# cryobondr-sense1-vlaqc-test2.net
KiCad netlist of a schematic drawn in EAGLE
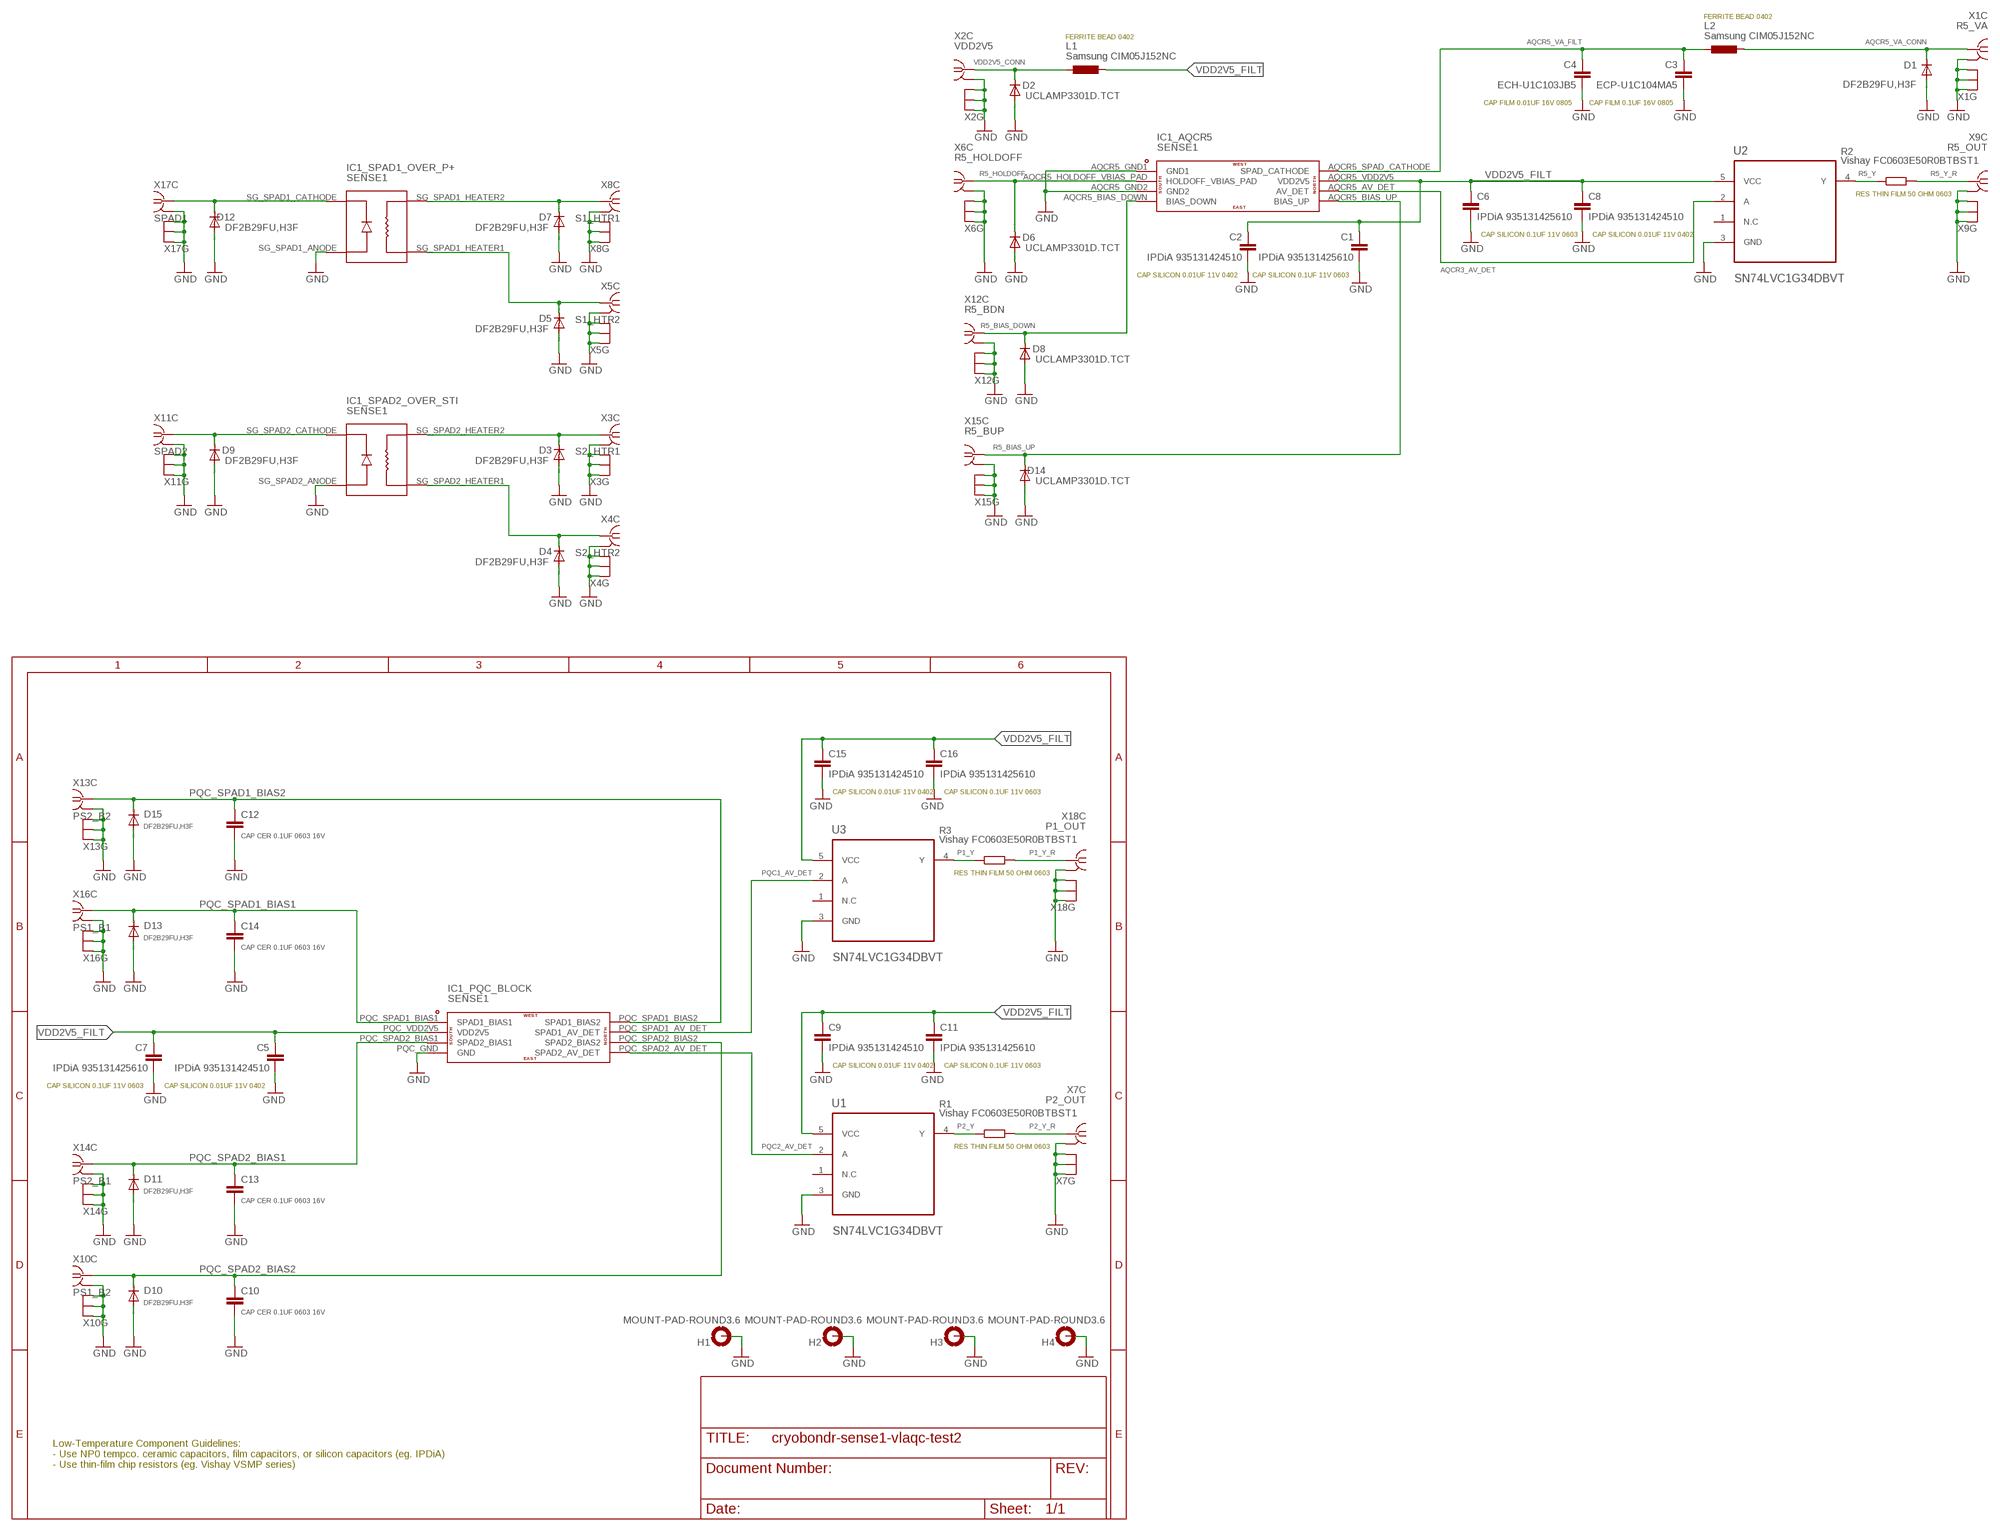
[diagram p0: schematic, sheet 1]

(export (version "E")
  (design (tool "Eeschema 10.0.6"))
  (components
    (comp (ref "C1")
      (value "IPDiA 935131425610")
      (footprint "eagle-import:C0603")
      (libsource (lib "eagle-import") (part "C-EUC0603"))
    )
    (comp (ref "C2")
      (value "IPDiA 935131424510")
      (footprint "eagle-import:C0402")
      (libsource (lib "eagle-import") (part "C-EUC0402"))
    )
    (comp (ref "C3")
      (value "ECP-U1C104MA5")
      (footprint "eagle-import:C0805")
      (libsource (lib "eagle-import") (part "C-EUC0805"))
    )
    (comp (ref "C4")
      (value "ECH-U1C103JB5")
      (footprint "eagle-import:C0805")
      (libsource (lib "eagle-import") (part "C-EUC0805"))
    )
    (comp (ref "C5")
      (value "IPDiA 935131424510")
      (footprint "eagle-import:C0402")
      (libsource (lib "eagle-import") (part "C-EUC0402"))
    )
    (comp (ref "C6")
      (value "IPDiA 935131425610")
      (footprint "eagle-import:C0603")
      (libsource (lib "eagle-import") (part "C-EUC0603"))
    )
    (comp (ref "C7")
      (value "IPDiA 935131425610")
      (footprint "eagle-import:C0603")
      (libsource (lib "eagle-import") (part "C-EUC0603"))
    )
    (comp (ref "C8")
      (value "IPDiA 935131424510")
      (footprint "eagle-import:C0402")
      (libsource (lib "eagle-import") (part "C-EUC0402"))
    )
    (comp (ref "C9")
      (value "IPDiA 935131424510")
      (footprint "eagle-import:C0402")
      (libsource (lib "eagle-import") (part "C-EUC0402"))
    )
    (comp (ref "C10")
      (value "CAP CER 0.1UF 0603 16V")
      (footprint "eagle-import:C0603")
      (libsource (lib "eagle-import") (part "C-EUC0603"))
    )
    (comp (ref "C11")
      (value "IPDiA 935131425610")
      (footprint "eagle-import:C0603")
      (libsource (lib "eagle-import") (part "C-EUC0603"))
    )
    (comp (ref "C12")
      (value "CAP CER 0.1UF 0603 16V")
      (footprint "eagle-import:C0603")
      (libsource (lib "eagle-import") (part "C-EUC0603"))
    )
    (comp (ref "C13")
      (value "CAP CER 0.1UF 0603 16V")
      (footprint "eagle-import:C0603")
      (libsource (lib "eagle-import") (part "C-EUC0603"))
    )
    (comp (ref "C14")
      (value "CAP CER 0.1UF 0603 16V")
      (footprint "eagle-import:C0603")
      (libsource (lib "eagle-import") (part "C-EUC0603"))
    )
    (comp (ref "C15")
      (value "IPDiA 935131424510")
      (footprint "eagle-import:C0402")
      (libsource (lib "eagle-import") (part "C-EUC0402"))
    )
    (comp (ref "C16")
      (value "IPDiA 935131425610")
      (footprint "eagle-import:C0603")
      (libsource (lib "eagle-import") (part "C-EUC0603"))
    )
    (comp (ref "D1")
      (value "DF2B29FU,H3F")
      (footprint "eagle-import:SOD323-R")
      (libsource (lib "eagle-import") (part "DIODE-SOD323-R"))
    )
    (comp (ref "D2")
      (value "UCLAMP3301D.TCT")
      (footprint "eagle-import:SOD323-R")
      (libsource (lib "eagle-import") (part "DIODE-SOD323-R"))
    )
    (comp (ref "D3")
      (value "DF2B29FU,H3F")
      (footprint "eagle-import:SOD323-R")
      (libsource (lib "eagle-import") (part "DIODE-SOD323-R"))
    )
    (comp (ref "D4")
      (value "DF2B29FU,H3F")
      (footprint "eagle-import:SOD323-R")
      (libsource (lib "eagle-import") (part "DIODE-SOD323-R"))
    )
    (comp (ref "D5")
      (value "DF2B29FU,H3F")
      (footprint "eagle-import:SOD323-R")
      (libsource (lib "eagle-import") (part "DIODE-SOD323-R"))
    )
    (comp (ref "D6")
      (value "UCLAMP3301D.TCT")
      (footprint "eagle-import:SOD323-R")
      (libsource (lib "eagle-import") (part "DIODE-SOD323-R"))
    )
    (comp (ref "D7")
      (value "DF2B29FU,H3F")
      (footprint "eagle-import:SOD323-R")
      (libsource (lib "eagle-import") (part "DIODE-SOD323-R"))
    )
    (comp (ref "D8")
      (value "UCLAMP3301D.TCT")
      (footprint "eagle-import:SOD323-R")
      (libsource (lib "eagle-import") (part "DIODE-SOD323-R"))
    )
    (comp (ref "D9")
      (value "DF2B29FU,H3F")
      (footprint "eagle-import:SOD323-R")
      (libsource (lib "eagle-import") (part "DIODE-SOD323-R"))
    )
    (comp (ref "D10")
      (value "DF2B29FU,H3F")
      (footprint "eagle-import:SOD323-R")
      (libsource (lib "eagle-import") (part "DIODE-SOD323-R"))
    )
    (comp (ref "D11")
      (value "DF2B29FU,H3F")
      (footprint "eagle-import:SOD323-R")
      (libsource (lib "eagle-import") (part "DIODE-SOD323-R"))
    )
    (comp (ref "D12")
      (value "DF2B29FU,H3F")
      (footprint "eagle-import:SOD323-R")
      (libsource (lib "eagle-import") (part "DIODE-SOD323-R"))
    )
    (comp (ref "D13")
      (value "DF2B29FU,H3F")
      (footprint "eagle-import:SOD323-R")
      (libsource (lib "eagle-import") (part "DIODE-SOD323-R"))
    )
    (comp (ref "D14")
      (value "UCLAMP3301D.TCT")
      (footprint "eagle-import:SOD323-R")
      (libsource (lib "eagle-import") (part "DIODE-SOD323-R"))
    )
    (comp (ref "D15")
      (value "DF2B29FU,H3F")
      (footprint "eagle-import:SOD323-R")
      (libsource (lib "eagle-import") (part "DIODE-SOD323-R"))
    )
    (comp (ref "H1")
      (value "MOUNT-PAD-ROUND3.6")
      (footprint "eagle-import:3,6-PAD")
      (libsource (lib "eagle-import") (part "MOUNT-PAD-ROUND3.6"))
    )
    (comp (ref "H2")
      (value "MOUNT-PAD-ROUND3.6")
      (footprint "eagle-import:3,6-PAD")
      (libsource (lib "eagle-import") (part "MOUNT-PAD-ROUND3.6"))
    )
    (comp (ref "H3")
      (value "MOUNT-PAD-ROUND3.6")
      (footprint "eagle-import:3,6-PAD")
      (libsource (lib "eagle-import") (part "MOUNT-PAD-ROUND3.6"))
    )
    (comp (ref "H4")
      (value "MOUNT-PAD-ROUND3.6")
      (footprint "eagle-import:3,6-PAD")
      (libsource (lib "eagle-import") (part "MOUNT-PAD-ROUND3.6"))
    )
    (comp (ref "IC1")
      (value "SENSE1")
      (footprint "eagle-import:SENSE1-WIREBOND-VLAQC-TEST2")
      (libsource (lib "eagle-import") (part "SENSE1-WIREBOND-VLAQC-TEST2"))
    )
    (comp (ref "L1")
      (value "Samsung CIM05J152NC")
      (footprint "eagle-import:R0402")
      (libsource (lib "eagle-import") (part "INDUCTOR0402"))
    )
    (comp (ref "L2")
      (value "Samsung CIM05J152NC")
      (footprint "eagle-import:R0402")
      (libsource (lib "eagle-import") (part "INDUCTOR0402"))
    )
    (comp (ref "R1")
      (value "Vishay FC0603E50R0BTBST1")
      (footprint "eagle-import:R0603")
      (libsource (lib "eagle-import") (part "R-EU_R0603"))
    )
    (comp (ref "R2")
      (value "Vishay FC0603E50R0BTBST1")
      (footprint "eagle-import:R0603")
      (libsource (lib "eagle-import") (part "R-EU_R0603"))
    )
    (comp (ref "R3")
      (value "Vishay FC0603E50R0BTBST1")
      (footprint "eagle-import:R0603")
      (libsource (lib "eagle-import") (part "R-EU_R0603"))
    )
    (comp (ref "U1")
      (value "SN74LVC1G34DBVT")
      (footprint "eagle-import:SOT95P280X145-5N")
      (fields (field (name "SPICEPREFIX") "X"))
      (libsource (lib "eagle-import") (part "SN74LVC1G34DBVT"))
    )
    (comp (ref "U2")
      (value "SN74LVC1G34DBVT")
      (footprint "eagle-import:SOT95P280X145-5N")
      (fields (field (name "SPICEPREFIX") "X"))
      (libsource (lib "eagle-import") (part "SN74LVC1G34DBVT"))
    )
    (comp (ref "U3")
      (value "SN74LVC1G34DBVT")
      (footprint "eagle-import:SOT95P280X145-5N")
      (fields (field (name "SPICEPREFIX") "X"))
      (libsource (lib "eagle-import") (part "SN74LVC1G34DBVT"))
    )
    (comp (ref "X1")
      (value "R5_VA")
      (footprint "eagle-import:MMCX-SMT-BIGPADS")
      (libsource (lib "eagle-import") (part "MMCXBIGPAD"))
    )
    (comp (ref "X2")
      (value "VDD2V5")
      (footprint "eagle-import:MMCX-SMT-BIGPADS")
      (libsource (lib "eagle-import") (part "MMCXBIGPAD"))
    )
    (comp (ref "X3")
      (value "S2_HTR1")
      (footprint "eagle-import:MMCX-SMT-BIGPADS")
      (libsource (lib "eagle-import") (part "MMCXBIGPAD"))
    )
    (comp (ref "X4")
      (value "S2_HTR2")
      (footprint "eagle-import:MMCX-SMT-BIGPADS")
      (libsource (lib "eagle-import") (part "MMCXBIGPAD"))
    )
    (comp (ref "X5")
      (value "S1_HTR2")
      (footprint "eagle-import:MMCX-SMT-BIGPADS")
      (libsource (lib "eagle-import") (part "MMCXBIGPAD"))
    )
    (comp (ref "X6")
      (value "R5_HOLDOFF")
      (footprint "eagle-import:MMCX-SMT-BIGPADS")
      (libsource (lib "eagle-import") (part "MMCXBIGPAD"))
    )
    (comp (ref "X7")
      (value "P2_OUT")
      (footprint "eagle-import:MMCX-SMT-BIGPADS")
      (libsource (lib "eagle-import") (part "MMCXBIGPAD"))
    )
    (comp (ref "X8")
      (value "S1_HTR1")
      (footprint "eagle-import:MMCX-SMT-BIGPADS")
      (libsource (lib "eagle-import") (part "MMCXBIGPAD"))
    )
    (comp (ref "X9")
      (value "R5_OUT")
      (footprint "eagle-import:MMCX-SMT-BIGPADS")
      (libsource (lib "eagle-import") (part "MMCXBIGPAD"))
    )
    (comp (ref "X10")
      (value "PS1_B2")
      (footprint "eagle-import:MMCX-SMT-BIGPADS")
      (libsource (lib "eagle-import") (part "MMCXBIGPAD"))
    )
    (comp (ref "X11")
      (value "SPAD2")
      (footprint "eagle-import:MMCX-SMT-BIGPADS")
      (libsource (lib "eagle-import") (part "MMCXBIGPAD"))
    )
    (comp (ref "X12")
      (value "R5_BDN")
      (footprint "eagle-import:MMCX-SMT-BIGPADS")
      (libsource (lib "eagle-import") (part "MMCXBIGPAD"))
    )
    (comp (ref "X13")
      (value "PS2_B2")
      (footprint "eagle-import:MMCX-SMT-BIGPADS")
      (libsource (lib "eagle-import") (part "MMCXBIGPAD"))
    )
    (comp (ref "X14")
      (value "PS2_B1")
      (footprint "eagle-import:MMCX-SMT-BIGPADS")
      (libsource (lib "eagle-import") (part "MMCXBIGPAD"))
    )
    (comp (ref "X15")
      (value "R5_BUP")
      (footprint "eagle-import:MMCX-SMT-BIGPADS")
      (libsource (lib "eagle-import") (part "MMCXBIGPAD"))
    )
    (comp (ref "X16")
      (value "PS1_B1")
      (footprint "eagle-import:MMCX-SMT-BIGPADS")
      (libsource (lib "eagle-import") (part "MMCXBIGPAD"))
    )
    (comp (ref "X17")
      (value "SPAD1")
      (footprint "eagle-import:MMCX-SMT-BIGPADS")
      (libsource (lib "eagle-import") (part "MMCXBIGPAD"))
    )
    (comp (ref "X18")
      (value "P1_OUT")
      (footprint "eagle-import:MMCX-SMT-BIGPADS")
      (libsource (lib "eagle-import") (part "MMCXBIGPAD"))
    )
  )
  (nets
    (net (code "1") (name "/AQCR3_AV_DET") (class "Default")
      (node (ref "IC1") (pin "AQCR5_AV_DET") (pinfunction "AV_DET_AQCR5_AV_DET") (pintype "bidirectional"))
      (node (ref "U2") (pin "2") (pinfunction "A_2") (pintype "input"))
    )
    (net (code "2") (name "/AQCR5_VA_CONN") (class "Default")
      (node (ref "D1") (pin "C") (pinfunction "C_C") (pintype "passive"))
      (node (ref "L2") (pin "2") (pinfunction "P$2_2") (pintype "bidirectional"))
      (node (ref "X1") (pin "S") (pinfunction "1_S") (pintype "passive"))
    )
    (net (code "3") (name "/AQCR5_VA_FILT") (class "Default")
      (node (ref "C3") (pin "1") (pinfunction "1_1") (pintype "passive"))
      (node (ref "C4") (pin "1") (pinfunction "1_1") (pintype "passive"))
      (node (ref "IC1") (pin "AQCR5_SPAD_CATHODE") (pinfunction "SPAD_CATHODE_AQCR5_SPAD_CATHODE") (pintype "bidirectional"))
      (node (ref "L2") (pin "1") (pinfunction "P$1_1") (pintype "bidirectional"))
    )
    (net (code "4") (name "/P1_Y") (class "Default")
      (node (ref "R3") (pin "1") (pinfunction "1_1") (pintype "passive"))
      (node (ref "U3") (pin "4") (pinfunction "Y_4") (pintype "output"))
    )
    (net (code "5") (name "/P1_Y_R") (class "Default")
      (node (ref "R3") (pin "2") (pinfunction "2_2") (pintype "passive"))
      (node (ref "X18") (pin "S") (pinfunction "1_S") (pintype "passive"))
    )
    (net (code "6") (name "/P2_Y") (class "Default")
      (node (ref "R1") (pin "1") (pinfunction "1_1") (pintype "passive"))
      (node (ref "U1") (pin "4") (pinfunction "Y_4") (pintype "output"))
    )
    (net (code "7") (name "/P2_Y_R") (class "Default")
      (node (ref "R1") (pin "2") (pinfunction "2_2") (pintype "passive"))
      (node (ref "X7") (pin "S") (pinfunction "1_S") (pintype "passive"))
    )
    (net (code "8") (name "/PQC1_AV_DET") (class "Default")
      (node (ref "IC1") (pin "PQC_SPAD1_AV_DET") (pinfunction "SPAD1_AV_DET_PQC_SPAD1_AV_DET") (pintype "bidirectional"))
      (node (ref "U3") (pin "2") (pinfunction "A_2") (pintype "input"))
    )
    (net (code "9") (name "/PQC2_AV_DET") (class "Default")
      (node (ref "IC1") (pin "PQC_SPAD2_AV_DET") (pinfunction "SPAD2_AV_DET_PQC_SPAD2_AV_DET") (pintype "bidirectional"))
      (node (ref "U1") (pin "2") (pinfunction "A_2") (pintype "input"))
    )
    (net (code "10") (name "/PQC_SPAD1_BIAS1") (class "Default")
      (node (ref "C14") (pin "1") (pinfunction "1_1") (pintype "passive"))
      (node (ref "D13") (pin "C") (pinfunction "C_C") (pintype "passive"))
      (node (ref "IC1") (pin "PQC_SPAD1_BIAS1") (pinfunction "SPAD1_BIAS1_PQC_SPAD1_BIAS1") (pintype "bidirectional"))
      (node (ref "X16") (pin "S") (pinfunction "1_S") (pintype "passive"))
    )
    (net (code "11") (name "/PQC_SPAD1_BIAS2") (class "Default")
      (node (ref "C12") (pin "1") (pinfunction "1_1") (pintype "passive"))
      (node (ref "D15") (pin "C") (pinfunction "C_C") (pintype "passive"))
      (node (ref "IC1") (pin "PQC_SPAD1_BIAS2") (pinfunction "SPAD1_BIAS2_PQC_SPAD1_BIAS2") (pintype "bidirectional"))
      (node (ref "X13") (pin "S") (pinfunction "1_S") (pintype "passive"))
    )
    (net (code "12") (name "/PQC_SPAD2_BIAS1") (class "Default")
      (node (ref "C13") (pin "1") (pinfunction "1_1") (pintype "passive"))
      (node (ref "D11") (pin "C") (pinfunction "C_C") (pintype "passive"))
      (node (ref "IC1") (pin "PQC_SPAD2_BIAS1") (pinfunction "SPAD2_BIAS1_PQC_SPAD2_BIAS1") (pintype "bidirectional"))
      (node (ref "X14") (pin "S") (pinfunction "1_S") (pintype "passive"))
    )
    (net (code "13") (name "/PQC_SPAD2_BIAS2") (class "Default")
      (node (ref "C10") (pin "1") (pinfunction "1_1") (pintype "passive"))
      (node (ref "D10") (pin "C") (pinfunction "C_C") (pintype "passive"))
      (node (ref "IC1") (pin "PQC_SPAD2_BIAS2") (pinfunction "SPAD2_BIAS2_PQC_SPAD2_BIAS2") (pintype "bidirectional"))
      (node (ref "X10") (pin "S") (pinfunction "1_S") (pintype "passive"))
    )
    (net (code "14") (name "/R5_BIAS_DOWN") (class "Default")
      (node (ref "D8") (pin "C") (pinfunction "C_C") (pintype "passive"))
      (node (ref "IC1") (pin "AQCR5_BIAS_DOWN") (pinfunction "BIAS_DOWN_AQCR5_BIAS_DOWN") (pintype "bidirectional"))
      (node (ref "X12") (pin "S") (pinfunction "1_S") (pintype "passive"))
    )
    (net (code "15") (name "/R5_BIAS_UP") (class "Default")
      (node (ref "D14") (pin "C") (pinfunction "C_C") (pintype "passive"))
      (node (ref "IC1") (pin "AQCR5_BIAS_UP") (pinfunction "BIAS_UP_AQCR5_BIAS_UP") (pintype "bidirectional"))
      (node (ref "X15") (pin "S") (pinfunction "1_S") (pintype "passive"))
    )
    (net (code "16") (name "/R5_HOLDOFF") (class "Default")
      (node (ref "D6") (pin "C") (pinfunction "C_C") (pintype "passive"))
      (node (ref "IC1") (pin "AQCR5_HOLDOFF_VBIAS_PAD") (pinfunction "HOLDOFF_VBIAS_PAD_AQCR5_HOLDOFF_VBIAS_PAD") (pintype "bidirectional"))
      (node (ref "X6") (pin "S") (pinfunction "1_S") (pintype "passive"))
    )
    (net (code "17") (name "/R5_Y") (class "Default")
      (node (ref "R2") (pin "1") (pinfunction "1_1") (pintype "passive"))
      (node (ref "U2") (pin "4") (pinfunction "Y_4") (pintype "output"))
    )
    (net (code "18") (name "/R5_Y_R") (class "Default")
      (node (ref "R2") (pin "2") (pinfunction "2_2") (pintype "passive"))
      (node (ref "X9") (pin "S") (pinfunction "1_S") (pintype "passive"))
    )
    (net (code "19") (name "/VDD2V5_CONN") (class "Default")
      (node (ref "D2") (pin "C") (pinfunction "C_C") (pintype "passive"))
      (node (ref "L1") (pin "1") (pinfunction "P$1_1") (pintype "bidirectional"))
      (node (ref "X2") (pin "S") (pinfunction "1_S") (pintype "passive"))
    )
    (net (code "20") (name "GND") (class "Default")
      (node (ref "C1") (pin "2") (pinfunction "2_2") (pintype "passive"))
      (node (ref "C10") (pin "2") (pinfunction "2_2") (pintype "passive"))
      (node (ref "C11") (pin "2") (pinfunction "2_2") (pintype "passive"))
      (node (ref "C12") (pin "2") (pinfunction "2_2") (pintype "passive"))
      (node (ref "C13") (pin "2") (pinfunction "2_2") (pintype "passive"))
      (node (ref "C14") (pin "2") (pinfunction "2_2") (pintype "passive"))
      (node (ref "C15") (pin "2") (pinfunction "2_2") (pintype "passive"))
      (node (ref "C16") (pin "2") (pinfunction "2_2") (pintype "passive"))
      (node (ref "C2") (pin "2") (pinfunction "2_2") (pintype "passive"))
      (node (ref "C3") (pin "2") (pinfunction "2_2") (pintype "passive"))
      (node (ref "C4") (pin "2") (pinfunction "2_2") (pintype "passive"))
      (node (ref "C5") (pin "2") (pinfunction "2_2") (pintype "passive"))
      (node (ref "C6") (pin "2") (pinfunction "2_2") (pintype "passive"))
      (node (ref "C7") (pin "2") (pinfunction "2_2") (pintype "passive"))
      (node (ref "C8") (pin "2") (pinfunction "2_2") (pintype "passive"))
      (node (ref "C9") (pin "2") (pinfunction "2_2") (pintype "passive"))
      (node (ref "D1") (pin "A") (pinfunction "A_A") (pintype "passive"))
      (node (ref "D10") (pin "A") (pinfunction "A_A") (pintype "passive"))
      (node (ref "D11") (pin "A") (pinfunction "A_A") (pintype "passive"))
      (node (ref "D12") (pin "A") (pinfunction "A_A") (pintype "passive"))
      (node (ref "D13") (pin "A") (pinfunction "A_A") (pintype "passive"))
      (node (ref "D14") (pin "A") (pinfunction "A_A") (pintype "passive"))
      (node (ref "D15") (pin "A") (pinfunction "A_A") (pintype "passive"))
      (node (ref "D2") (pin "A") (pinfunction "A_A") (pintype "passive"))
      (node (ref "D3") (pin "A") (pinfunction "A_A") (pintype "passive"))
      (node (ref "D4") (pin "A") (pinfunction "A_A") (pintype "passive"))
      (node (ref "D5") (pin "A") (pinfunction "A_A") (pintype "passive"))
      (node (ref "D6") (pin "A") (pinfunction "A_A") (pintype "passive"))
      (node (ref "D7") (pin "A") (pinfunction "A_A") (pintype "passive"))
      (node (ref "D8") (pin "A") (pinfunction "A_A") (pintype "passive"))
      (node (ref "D9") (pin "A") (pinfunction "A_A") (pintype "passive"))
      (node (ref "H1") (pin "B3,6") (pinfunction "MOUNT_B3,6") (pintype "passive"))
      (node (ref "H2") (pin "B3,6") (pinfunction "MOUNT_B3,6") (pintype "passive"))
      (node (ref "H3") (pin "B3,6") (pinfunction "MOUNT_B3,6") (pintype "passive"))
      (node (ref "H4") (pin "B3,6") (pinfunction "MOUNT_B3,6") (pintype "passive"))
      (node (ref "IC1") (pin "AQCR5_GND1") (pinfunction "GND1_AQCR5_GND1") (pintype "bidirectional"))
      (node (ref "IC1") (pin "AQCR5_GND2") (pinfunction "GND2_AQCR5_GND2") (pintype "bidirectional"))
      (node (ref "IC1") (pin "PQC_GND") (pinfunction "GND_PQC_GND") (pintype "bidirectional"))
      (node (ref "IC1") (pin "SG_SPAD1_ANODE") (pinfunction "SPAD_ANODE_SG_SPAD1_ANODE") (pintype "bidirectional"))
      (node (ref "IC1") (pin "SG_SPAD2_ANODE") (pinfunction "SPAD_ANODE_SG_SPAD2_ANODE") (pintype "bidirectional"))
      (node (ref "U1") (pin "3") (pinfunction "GND_3") (pintype "passive"))
      (node (ref "U2") (pin "3") (pinfunction "GND_3") (pintype "passive"))
      (node (ref "U3") (pin "3") (pinfunction "GND_3") (pintype "passive"))
      (node (ref "X1") (pin "G1") (pinfunction "GND_G1") (pintype "power_in"))
      (node (ref "X1") (pin "G2") (pinfunction "GND_G2") (pintype "power_in"))
      (node (ref "X1") (pin "G3") (pinfunction "GND_G3") (pintype "power_in"))
      (node (ref "X1") (pin "G4") (pinfunction "GND_G4") (pintype "power_in"))
      (node (ref "X10") (pin "G1") (pinfunction "GND_G1") (pintype "power_in"))
      (node (ref "X10") (pin "G2") (pinfunction "GND_G2") (pintype "power_in"))
      (node (ref "X10") (pin "G3") (pinfunction "GND_G3") (pintype "power_in"))
      (node (ref "X10") (pin "G4") (pinfunction "GND_G4") (pintype "power_in"))
      (node (ref "X11") (pin "G1") (pinfunction "GND_G1") (pintype "power_in"))
      (node (ref "X11") (pin "G2") (pinfunction "GND_G2") (pintype "power_in"))
      (node (ref "X11") (pin "G3") (pinfunction "GND_G3") (pintype "power_in"))
      (node (ref "X11") (pin "G4") (pinfunction "GND_G4") (pintype "power_in"))
      (node (ref "X12") (pin "G1") (pinfunction "GND_G1") (pintype "power_in"))
      (node (ref "X12") (pin "G2") (pinfunction "GND_G2") (pintype "power_in"))
      (node (ref "X12") (pin "G3") (pinfunction "GND_G3") (pintype "power_in"))
      (node (ref "X12") (pin "G4") (pinfunction "GND_G4") (pintype "power_in"))
      (node (ref "X13") (pin "G1") (pinfunction "GND_G1") (pintype "power_in"))
      (node (ref "X13") (pin "G2") (pinfunction "GND_G2") (pintype "power_in"))
      (node (ref "X13") (pin "G3") (pinfunction "GND_G3") (pintype "power_in"))
      (node (ref "X13") (pin "G4") (pinfunction "GND_G4") (pintype "power_in"))
      (node (ref "X14") (pin "G1") (pinfunction "GND_G1") (pintype "power_in"))
      (node (ref "X14") (pin "G2") (pinfunction "GND_G2") (pintype "power_in"))
      (node (ref "X14") (pin "G3") (pinfunction "GND_G3") (pintype "power_in"))
      (node (ref "X14") (pin "G4") (pinfunction "GND_G4") (pintype "power_in"))
      (node (ref "X15") (pin "G1") (pinfunction "GND_G1") (pintype "power_in"))
      (node (ref "X15") (pin "G2") (pinfunction "GND_G2") (pintype "power_in"))
      (node (ref "X15") (pin "G3") (pinfunction "GND_G3") (pintype "power_in"))
      (node (ref "X15") (pin "G4") (pinfunction "GND_G4") (pintype "power_in"))
      (node (ref "X16") (pin "G1") (pinfunction "GND_G1") (pintype "power_in"))
      (node (ref "X16") (pin "G2") (pinfunction "GND_G2") (pintype "power_in"))
      (node (ref "X16") (pin "G3") (pinfunction "GND_G3") (pintype "power_in"))
      (node (ref "X16") (pin "G4") (pinfunction "GND_G4") (pintype "power_in"))
      (node (ref "X17") (pin "G1") (pinfunction "GND_G1") (pintype "power_in"))
      (node (ref "X17") (pin "G2") (pinfunction "GND_G2") (pintype "power_in"))
      (node (ref "X17") (pin "G3") (pinfunction "GND_G3") (pintype "power_in"))
      (node (ref "X17") (pin "G4") (pinfunction "GND_G4") (pintype "power_in"))
      (node (ref "X18") (pin "G1") (pinfunction "GND_G1") (pintype "power_in"))
      (node (ref "X18") (pin "G2") (pinfunction "GND_G2") (pintype "power_in"))
      (node (ref "X18") (pin "G3") (pinfunction "GND_G3") (pintype "power_in"))
      (node (ref "X18") (pin "G4") (pinfunction "GND_G4") (pintype "power_in"))
      (node (ref "X2") (pin "G1") (pinfunction "GND_G1") (pintype "power_in"))
      (node (ref "X2") (pin "G2") (pinfunction "GND_G2") (pintype "power_in"))
      (node (ref "X2") (pin "G3") (pinfunction "GND_G3") (pintype "power_in"))
      (node (ref "X2") (pin "G4") (pinfunction "GND_G4") (pintype "power_in"))
      (node (ref "X3") (pin "G1") (pinfunction "GND_G1") (pintype "power_in"))
      (node (ref "X3") (pin "G2") (pinfunction "GND_G2") (pintype "power_in"))
      (node (ref "X3") (pin "G3") (pinfunction "GND_G3") (pintype "power_in"))
      (node (ref "X3") (pin "G4") (pinfunction "GND_G4") (pintype "power_in"))
      (node (ref "X4") (pin "G1") (pinfunction "GND_G1") (pintype "power_in"))
      (node (ref "X4") (pin "G2") (pinfunction "GND_G2") (pintype "power_in"))
      (node (ref "X4") (pin "G3") (pinfunction "GND_G3") (pintype "power_in"))
      (node (ref "X4") (pin "G4") (pinfunction "GND_G4") (pintype "power_in"))
      (node (ref "X5") (pin "G1") (pinfunction "GND_G1") (pintype "power_in"))
      (node (ref "X5") (pin "G2") (pinfunction "GND_G2") (pintype "power_in"))
      (node (ref "X5") (pin "G3") (pinfunction "GND_G3") (pintype "power_in"))
      (node (ref "X5") (pin "G4") (pinfunction "GND_G4") (pintype "power_in"))
      (node (ref "X6") (pin "G1") (pinfunction "GND_G1") (pintype "power_in"))
      (node (ref "X6") (pin "G2") (pinfunction "GND_G2") (pintype "power_in"))
      (node (ref "X6") (pin "G3") (pinfunction "GND_G3") (pintype "power_in"))
      (node (ref "X6") (pin "G4") (pinfunction "GND_G4") (pintype "power_in"))
      (node (ref "X7") (pin "G1") (pinfunction "GND_G1") (pintype "power_in"))
      (node (ref "X7") (pin "G2") (pinfunction "GND_G2") (pintype "power_in"))
      (node (ref "X7") (pin "G3") (pinfunction "GND_G3") (pintype "power_in"))
      (node (ref "X7") (pin "G4") (pinfunction "GND_G4") (pintype "power_in"))
      (node (ref "X8") (pin "G1") (pinfunction "GND_G1") (pintype "power_in"))
      (node (ref "X8") (pin "G2") (pinfunction "GND_G2") (pintype "power_in"))
      (node (ref "X8") (pin "G3") (pinfunction "GND_G3") (pintype "power_in"))
      (node (ref "X8") (pin "G4") (pinfunction "GND_G4") (pintype "power_in"))
      (node (ref "X9") (pin "G1") (pinfunction "GND_G1") (pintype "power_in"))
      (node (ref "X9") (pin "G2") (pinfunction "GND_G2") (pintype "power_in"))
      (node (ref "X9") (pin "G3") (pinfunction "GND_G3") (pintype "power_in"))
      (node (ref "X9") (pin "G4") (pinfunction "GND_G4") (pintype "power_in"))
    )
    (net (code "21") (name "Net-(IC1C-SPAD_CATHODE)") (class "Default")
      (node (ref "D12") (pin "C") (pinfunction "C_C") (pintype "passive"))
      (node (ref "IC1") (pin "SG_SPAD1_CATHODE") (pinfunction "SPAD_CATHODE_SG_SPAD1_CATHODE") (pintype "bidirectional"))
      (node (ref "X17") (pin "S") (pinfunction "1_S") (pintype "passive"))
    )
    (net (code "22") (name "Net-(IC1C-SPAD_HEATER1)") (class "Default")
      (node (ref "D5") (pin "C") (pinfunction "C_C") (pintype "passive"))
      (node (ref "IC1") (pin "SG_SPAD1_HEATER1") (pinfunction "SPAD_HEATER1_SG_SPAD1_HEATER1") (pintype "bidirectional"))
      (node (ref "X5") (pin "S") (pinfunction "1_S") (pintype "passive"))
    )
    (net (code "23") (name "Net-(IC1C-SPAD_HEATER2)") (class "Default")
      (node (ref "D7") (pin "C") (pinfunction "C_C") (pintype "passive"))
      (node (ref "IC1") (pin "SG_SPAD1_HEATER2") (pinfunction "SPAD_HEATER2_SG_SPAD1_HEATER2") (pintype "bidirectional"))
      (node (ref "X8") (pin "S") (pinfunction "1_S") (pintype "passive"))
    )
    (net (code "24") (name "Net-(IC1D-SPAD_CATHODE)") (class "Default")
      (node (ref "D9") (pin "C") (pinfunction "C_C") (pintype "passive"))
      (node (ref "IC1") (pin "SG_SPAD2_CATHODE") (pinfunction "SPAD_CATHODE_SG_SPAD2_CATHODE") (pintype "bidirectional"))
      (node (ref "X11") (pin "S") (pinfunction "1_S") (pintype "passive"))
    )
    (net (code "25") (name "Net-(IC1D-SPAD_HEATER1)") (class "Default")
      (node (ref "D4") (pin "C") (pinfunction "C_C") (pintype "passive"))
      (node (ref "IC1") (pin "SG_SPAD2_HEATER1") (pinfunction "SPAD_HEATER1_SG_SPAD2_HEATER1") (pintype "bidirectional"))
      (node (ref "X4") (pin "S") (pinfunction "1_S") (pintype "passive"))
    )
    (net (code "26") (name "Net-(IC1D-SPAD_HEATER2)") (class "Default")
      (node (ref "D3") (pin "C") (pinfunction "C_C") (pintype "passive"))
      (node (ref "IC1") (pin "SG_SPAD2_HEATER2") (pinfunction "SPAD_HEATER2_SG_SPAD2_HEATER2") (pintype "bidirectional"))
      (node (ref "X3") (pin "S") (pinfunction "1_S") (pintype "passive"))
    )
    (net (code "27") (name "VDD2V5_FILT") (class "Default")
      (node (ref "C1") (pin "1") (pinfunction "1_1") (pintype "passive"))
      (node (ref "C11") (pin "1") (pinfunction "1_1") (pintype "passive"))
      (node (ref "C15") (pin "1") (pinfunction "1_1") (pintype "passive"))
      (node (ref "C16") (pin "1") (pinfunction "1_1") (pintype "passive"))
      (node (ref "C2") (pin "1") (pinfunction "1_1") (pintype "passive"))
      (node (ref "C5") (pin "1") (pinfunction "1_1") (pintype "passive"))
      (node (ref "C6") (pin "1") (pinfunction "1_1") (pintype "passive"))
      (node (ref "C7") (pin "1") (pinfunction "1_1") (pintype "passive"))
      (node (ref "C8") (pin "1") (pinfunction "1_1") (pintype "passive"))
      (node (ref "C9") (pin "1") (pinfunction "1_1") (pintype "passive"))
      (node (ref "IC1") (pin "AQCR5_VDD2V5") (pinfunction "VDD2V5_AQCR5_VDD2V5") (pintype "bidirectional"))
      (node (ref "IC1") (pin "PQC_VDD2V5") (pinfunction "VDD2V5_PQC_VDD2V5") (pintype "bidirectional"))
      (node (ref "L1") (pin "2") (pinfunction "P$2_2") (pintype "bidirectional"))
      (node (ref "U1") (pin "5") (pinfunction "VCC_5") (pintype "power_in"))
      (node (ref "U2") (pin "5") (pinfunction "VCC_5") (pintype "power_in"))
      (node (ref "U3") (pin "5") (pinfunction "VCC_5") (pintype "power_in"))
    )
    (net (code "28") (name "unconnected-(U1-N.C-Pad1)") (class "Default")
      (node (ref "U1") (pin "1") (pinfunction "N.C_1") (pintype "no_connect"))
    )
    (net (code "29") (name "unconnected-(U2-N.C-Pad1)") (class "Default")
      (node (ref "U2") (pin "1") (pinfunction "N.C_1") (pintype "no_connect"))
    )
    (net (code "30") (name "unconnected-(U3-N.C-Pad1)") (class "Default")
      (node (ref "U3") (pin "1") (pinfunction "N.C_1") (pintype "no_connect"))
    )
  )
)
